# sonar_hotfix.net
KiCad netlist of a schematic drawn in EAGLE
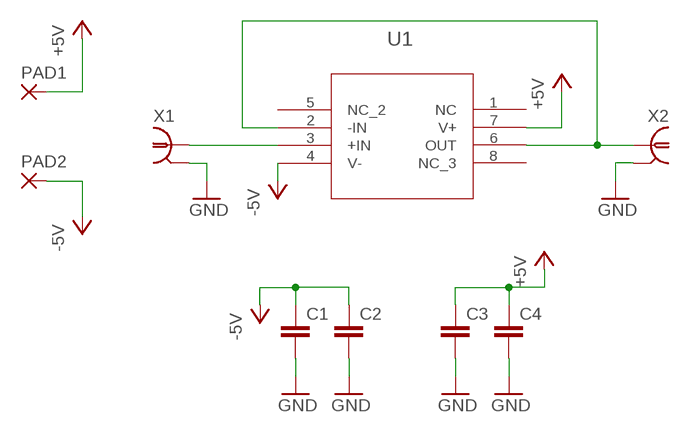
[diagram p0: schematic, sheet 1]

(export (version "E")
  (design (tool "Eeschema 10.0.6"))
  (components
    (comp (ref "C1")
      (value "C-EUC0603")
      (footprint "eagle-import:C0603")
      (libsource (lib "eagle-import") (part "C-EUC0603"))
    )
    (comp (ref "C2")
      (value "C-EUC0603")
      (footprint "eagle-import:C0603")
      (libsource (lib "eagle-import") (part "C-EUC0603"))
    )
    (comp (ref "C3")
      (value "C-EUC0603")
      (footprint "eagle-import:C0603")
      (libsource (lib "eagle-import") (part "C-EUC0603"))
    )
    (comp (ref "C4")
      (value "C-EUC0603")
      (footprint "eagle-import:C0603")
      (libsource (lib "eagle-import") (part "C-EUC0603"))
    )
    (comp (ref "PAD1")
      (value "WIREPADSMD5-2,5")
      (footprint "eagle-import:5-2,5")
      (libsource (lib "eagle-import") (part "WIREPADSMD5-2,5"))
    )
    (comp (ref "PAD2")
      (value "WIREPADSMD5-2,5")
      (footprint "eagle-import:5-2,5")
      (libsource (lib "eagle-import") (part "WIREPADSMD5-2,5"))
    )
    (comp (ref "U1")
      (value "LTC6240SO-8")
      (footprint "eagle-import:SO-8")
      (libsource (lib "eagle-import") (part "LTC6240SO-8"))
    )
    (comp (ref "X1")
      (value "0731000105")
      (footprint "eagle-import:0731000105")
      (libsource (lib "eagle-import") (part "0731000105"))
    )
    (comp (ref "X2")
      (value "0731000105")
      (footprint "eagle-import:0731000105")
      (libsource (lib "eagle-import") (part "0731000105"))
    )
  )
  (nets
    (net (code "1") (name "+5V") (class "Default")
      (node (ref "C3") (pin "1") (pinfunction "1_1") (pintype "passive"))
      (node (ref "C4") (pin "1") (pinfunction "1_1") (pintype "passive"))
      (node (ref "PAD1") (pin "1") (pinfunction "P_1") (pintype "passive"))
      (node (ref "U1") (pin "7") (pinfunction "V+_7") (pintype "power_in"))
    )
    (net (code "2") (name "-5V") (class "Default")
      (node (ref "C1") (pin "1") (pinfunction "1_1") (pintype "passive"))
      (node (ref "C2") (pin "1") (pinfunction "1_1") (pintype "passive"))
      (node (ref "PAD2") (pin "1") (pinfunction "P_1") (pintype "passive"))
      (node (ref "U1") (pin "4") (pinfunction "V-_4") (pintype "power_in"))
    )
    (net (code "3") (name "GND") (class "Default")
      (node (ref "C1") (pin "2") (pinfunction "2_2") (pintype "passive"))
      (node (ref "C2") (pin "2") (pinfunction "2_2") (pintype "passive"))
      (node (ref "C3") (pin "2") (pinfunction "2_2") (pintype "passive"))
      (node (ref "C4") (pin "2") (pinfunction "2_2") (pintype "passive"))
      (node (ref "X1") (pin "P$1") (pinfunction "2_P$1") (pintype "passive"))
      (node (ref "X1") (pin "P$2") (pinfunction "2_P$2") (pintype "passive"))
      (node (ref "X2") (pin "P$1") (pinfunction "2_P$1") (pintype "passive"))
      (node (ref "X2") (pin "P$2") (pinfunction "2_P$2") (pintype "passive"))
    )
    (net (code "4") (name "Net-(U1-+IN)") (class "Default")
      (node (ref "U1") (pin "3") (pinfunction "+IN_3") (pintype "input"))
      (node (ref "X1") (pin "P$3") (pinfunction "1_P$3") (pintype "passive"))
    )
    (net (code "5") (name "Net-(U1--IN)") (class "Default")
      (node (ref "U1") (pin "2") (pinfunction "-IN_2") (pintype "input"))
      (node (ref "U1") (pin "6") (pinfunction "OUT_6") (pintype "output"))
      (node (ref "X2") (pin "P$3") (pinfunction "1_P$3") (pintype "passive"))
    )
    (net (code "6") (name "unconnected-(U1-NC-Pad1)") (class "Default")
      (node (ref "U1") (pin "1") (pinfunction "NC_1") (pintype "no_connect"))
    )
    (net (code "7") (name "unconnected-(U1-NC_2-Pad5)") (class "Default")
      (node (ref "U1") (pin "5") (pinfunction "NC_2_5") (pintype "no_connect"))
    )
    (net (code "8") (name "unconnected-(U1-NC_3-Pad8)") (class "Default")
      (node (ref "U1") (pin "8") (pinfunction "NC_3_8") (pintype "no_connect"))
    )
  )
)
